# spider_tx4.net
KiCad netlist of a schematic drawn in EAGLE
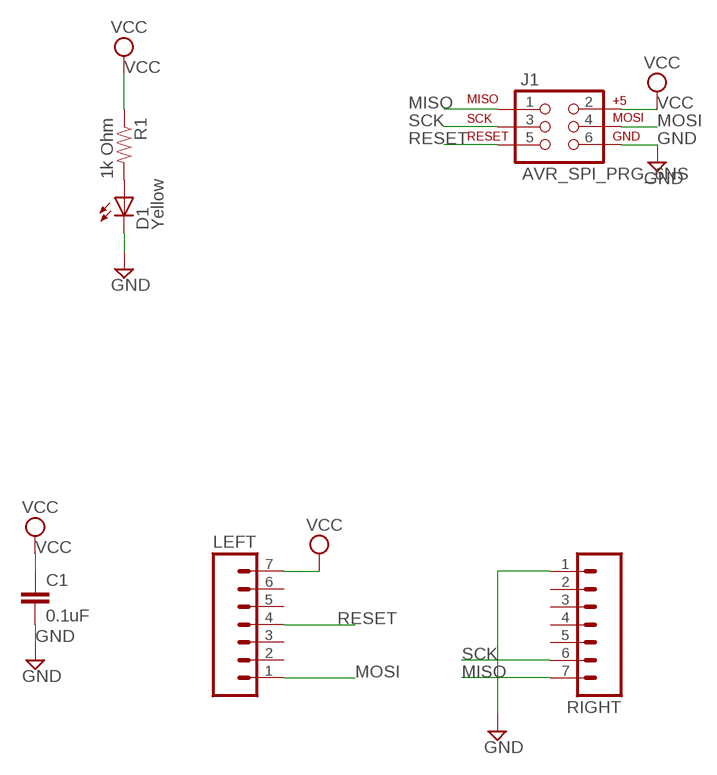
[diagram p0: schematic, sheet 1]

(export (version "E")
  (design (tool "Eeschema 10.0.6"))
  (components
    (comp (ref "C1")
      (value "0.1uF")
      (footprint "eagle-import:1206")
      (libsource (lib "eagle-import") (part "CAP1206"))
    )
    (comp (ref "D1")
      (value "Yellow")
      (footprint "eagle-import:LED-1206")
      (libsource (lib "eagle-import") (part "LED-YELLOWLILYPAD"))
    )
    (comp (ref "J1")
      (value "AVR_SPI_PRG_6NS")
      (footprint "eagle-import:2X3-NS")
      (libsource (lib "eagle-import") (part "AVR_SPI_PRG_6NS"))
    )
    (comp (ref "LEFT")
      (value "M07")
      (footprint "eagle-import:1X07")
      (libsource (lib "eagle-import") (part "M07"))
    )
    (comp (ref "R1")
      (value "1k Ohm")
      (footprint "eagle-import:1206")
      (libsource (lib "eagle-import") (part "RESISTOR1206"))
    )
    (comp (ref "RIGHT")
      (value "M07")
      (footprint "eagle-import:1X07")
      (libsource (lib "eagle-import") (part "M07"))
    )
  )
  (nets
    (net (code "1") (name "/MISO") (class "Default")
      (node (ref "J1") (pin "1") (pinfunction "1_1") (pintype "passive"))
      (node (ref "RIGHT") (pin "7") (pinfunction "7_7") (pintype "passive"))
    )
    (net (code "2") (name "/MOSI") (class "Default")
      (node (ref "J1") (pin "4") (pinfunction "4_4") (pintype "passive"))
      (node (ref "LEFT") (pin "1") (pinfunction "1_1") (pintype "passive"))
    )
    (net (code "3") (name "/RESET") (class "Default")
      (node (ref "J1") (pin "5") (pinfunction "5_5") (pintype "passive"))
      (node (ref "LEFT") (pin "4") (pinfunction "4_4") (pintype "passive"))
    )
    (net (code "4") (name "/SCK") (class "Default")
      (node (ref "J1") (pin "3") (pinfunction "3_3") (pintype "passive"))
      (node (ref "RIGHT") (pin "6") (pinfunction "6_6") (pintype "passive"))
    )
    (net (code "5") (name "GND") (class "Default")
      (node (ref "C1") (pin "2") (pinfunction "2_2") (pintype "passive"))
      (node (ref "D1") (pin "C") (pinfunction "C_C") (pintype "passive"))
      (node (ref "J1") (pin "6") (pinfunction "6_6") (pintype "passive"))
      (node (ref "RIGHT") (pin "1") (pinfunction "1_1") (pintype "passive"))
    )
    (net (code "6") (name "Net-(D1-PadA)") (class "Default")
      (node (ref "D1") (pin "A") (pinfunction "A_A") (pintype "passive"))
      (node (ref "R1") (pin "2") (pinfunction "2_2") (pintype "passive"))
    )
    (net (code "7") (name "VCC") (class "Default")
      (node (ref "C1") (pin "1") (pinfunction "1_1") (pintype "passive"))
      (node (ref "J1") (pin "2") (pinfunction "2_2") (pintype "passive"))
      (node (ref "LEFT") (pin "7") (pinfunction "7_7") (pintype "passive"))
      (node (ref "R1") (pin "1") (pinfunction "1_1") (pintype "passive"))
    )
    (net (code "8") (name "unconnected-(LEFT-Pad2)") (class "Default")
      (node (ref "LEFT") (pin "2") (pinfunction "2_2") (pintype "passive"))
    )
    (net (code "9") (name "unconnected-(LEFT-Pad3)") (class "Default")
      (node (ref "LEFT") (pin "3") (pinfunction "3_3") (pintype "passive"))
    )
    (net (code "10") (name "unconnected-(LEFT-Pad5)") (class "Default")
      (node (ref "LEFT") (pin "5") (pinfunction "5_5") (pintype "passive"))
    )
    (net (code "11") (name "unconnected-(LEFT-Pad6)") (class "Default")
      (node (ref "LEFT") (pin "6") (pinfunction "6_6") (pintype "passive"))
    )
    (net (code "12") (name "unconnected-(RIGHT-Pad2)") (class "Default")
      (node (ref "RIGHT") (pin "2") (pinfunction "2_2") (pintype "passive"))
    )
    (net (code "13") (name "unconnected-(RIGHT-Pad3)") (class "Default")
      (node (ref "RIGHT") (pin "3") (pinfunction "3_3") (pintype "passive"))
    )
    (net (code "14") (name "unconnected-(RIGHT-Pad4)") (class "Default")
      (node (ref "RIGHT") (pin "4") (pinfunction "4_4") (pintype "passive"))
    )
    (net (code "15") (name "unconnected-(RIGHT-Pad5)") (class "Default")
      (node (ref "RIGHT") (pin "5") (pinfunction "5_5") (pintype "passive"))
    )
  )
)
